# good.net
KiCad netlist of a schematic drawn in EAGLE
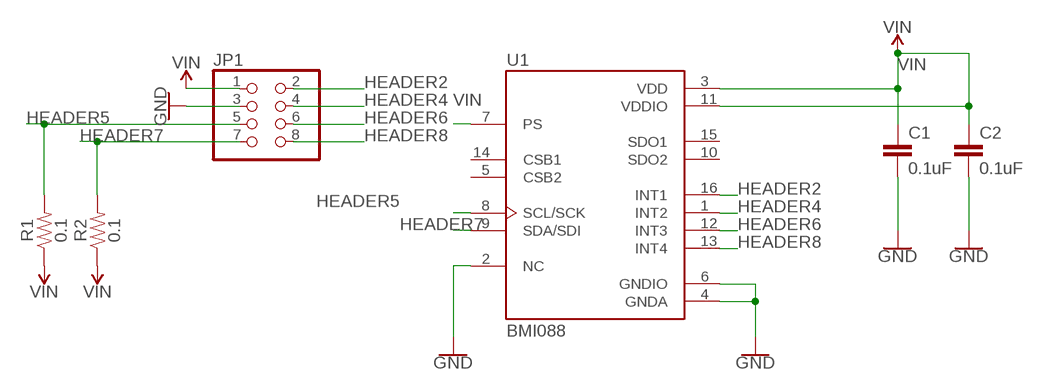
[diagram p0: schematic, sheet 1]

(export (version "E")
  (design (tool "Eeschema 10.0.6"))
  (components
    (comp (ref "C1")
      (value "0.1uF")
      (footprint "eagle-import:0402")
      (libsource (lib "eagle-import") (part "0.1UF-0402-16V-10%"))
    )
    (comp (ref "C2")
      (value "0.1uF")
      (footprint "eagle-import:0402")
      (libsource (lib "eagle-import") (part "0.1UF-0402-16V-10%"))
    )
    (comp (ref "JP1")
      (value "PINHD-2X4")
      (footprint "eagle-import:2X04")
      (libsource (lib "eagle-import") (part "PINHD-2X4"))
    )
    (comp (ref "R1")
      (value "0.1")
      (footprint "eagle-import:0603")
      (libsource (lib "eagle-import") (part "0.1OHM-0603-1/3W-1%"))
    )
    (comp (ref "R2")
      (value "0.1")
      (footprint "eagle-import:0603")
      (libsource (lib "eagle-import") (part "0.1OHM-0603-1/3W-1%"))
    )
    (comp (ref "U1")
      (value "BMI088")
      (footprint "eagle-import:PQFN50P450X300X100-16N")
      (fields (field (name "MF") "Bosch Sensortec"))
      (libsource (lib "eagle-import") (part "BMI088"))
    )
  )
  (nets
    (net (code "1") (name "/HEADER2") (class "Default")
      (node (ref "JP1") (pin "2") (pinfunction "2_2") (pintype "passive"))
      (node (ref "U1") (pin "16") (pinfunction "INT1_16") (pintype "bidirectional"))
    )
    (net (code "2") (name "/HEADER4") (class "Default")
      (node (ref "JP1") (pin "4") (pinfunction "4_4") (pintype "passive"))
      (node (ref "U1") (pin "1") (pinfunction "INT2_1") (pintype "bidirectional"))
    )
    (net (code "3") (name "/HEADER5") (class "Default")
      (node (ref "JP1") (pin "5") (pinfunction "5_5") (pintype "passive"))
      (node (ref "R1") (pin "2") (pinfunction "2_2") (pintype "passive"))
      (node (ref "U1") (pin "8") (pinfunction "SCL/SCK_8") (pintype "input"))
    )
    (net (code "4") (name "/HEADER6") (class "Default")
      (node (ref "JP1") (pin "6") (pinfunction "6_6") (pintype "passive"))
      (node (ref "U1") (pin "12") (pinfunction "INT3_12") (pintype "bidirectional"))
    )
    (net (code "5") (name "/HEADER7") (class "Default")
      (node (ref "JP1") (pin "7") (pinfunction "7_7") (pintype "passive"))
      (node (ref "R2") (pin "2") (pinfunction "2_2") (pintype "passive"))
      (node (ref "U1") (pin "9") (pinfunction "SDA/SDI_9") (pintype "bidirectional"))
    )
    (net (code "6") (name "/HEADER8") (class "Default")
      (node (ref "JP1") (pin "8") (pinfunction "8_8") (pintype "passive"))
      (node (ref "U1") (pin "13") (pinfunction "INT4_13") (pintype "bidirectional"))
    )
    (net (code "7") (name "GND") (class "Default")
      (node (ref "C1") (pin "2") (pinfunction "2_2") (pintype "passive"))
      (node (ref "C2") (pin "2") (pinfunction "2_2") (pintype "passive"))
      (node (ref "JP1") (pin "3") (pinfunction "3_3") (pintype "passive"))
      (node (ref "U1") (pin "2") (pinfunction "NC_2") (pintype "passive"))
      (node (ref "U1") (pin "4") (pinfunction "GNDA_4") (pintype "power_in"))
      (node (ref "U1") (pin "6") (pinfunction "GNDIO_6") (pintype "power_in"))
    )
    (net (code "8") (name "VIN") (class "Default")
      (node (ref "C1") (pin "1") (pinfunction "1_1") (pintype "passive"))
      (node (ref "C2") (pin "1") (pinfunction "1_1") (pintype "passive"))
      (node (ref "JP1") (pin "1") (pinfunction "1_1") (pintype "passive"))
      (node (ref "R1") (pin "1") (pinfunction "1_1") (pintype "passive"))
      (node (ref "R2") (pin "1") (pinfunction "1_1") (pintype "passive"))
      (node (ref "U1") (pin "11") (pinfunction "VDDIO_11") (pintype "power_in"))
      (node (ref "U1") (pin "3") (pinfunction "VDD_3") (pintype "power_in"))
      (node (ref "U1") (pin "7") (pinfunction "PS_7") (pintype "input"))
    )
    (net (code "9") (name "unconnected-(U1-CSB1-Pad14)") (class "Default")
      (node (ref "U1") (pin "14") (pinfunction "CSB1_14") (pintype "input"))
    )
    (net (code "10") (name "unconnected-(U1-CSB2-Pad5)") (class "Default")
      (node (ref "U1") (pin "5") (pinfunction "CSB2_5") (pintype "input"))
    )
    (net (code "11") (name "unconnected-(U1-SDO1-Pad15)") (class "Default")
      (node (ref "U1") (pin "15") (pinfunction "SDO1_15") (pintype "output"))
    )
    (net (code "12") (name "unconnected-(U1-SDO2-Pad10)") (class "Default")
      (node (ref "U1") (pin "10") (pinfunction "SDO2_10") (pintype "output"))
    )
  )
)
